# PSU.net
KiCad netlist of a schematic drawn in Altium Designer
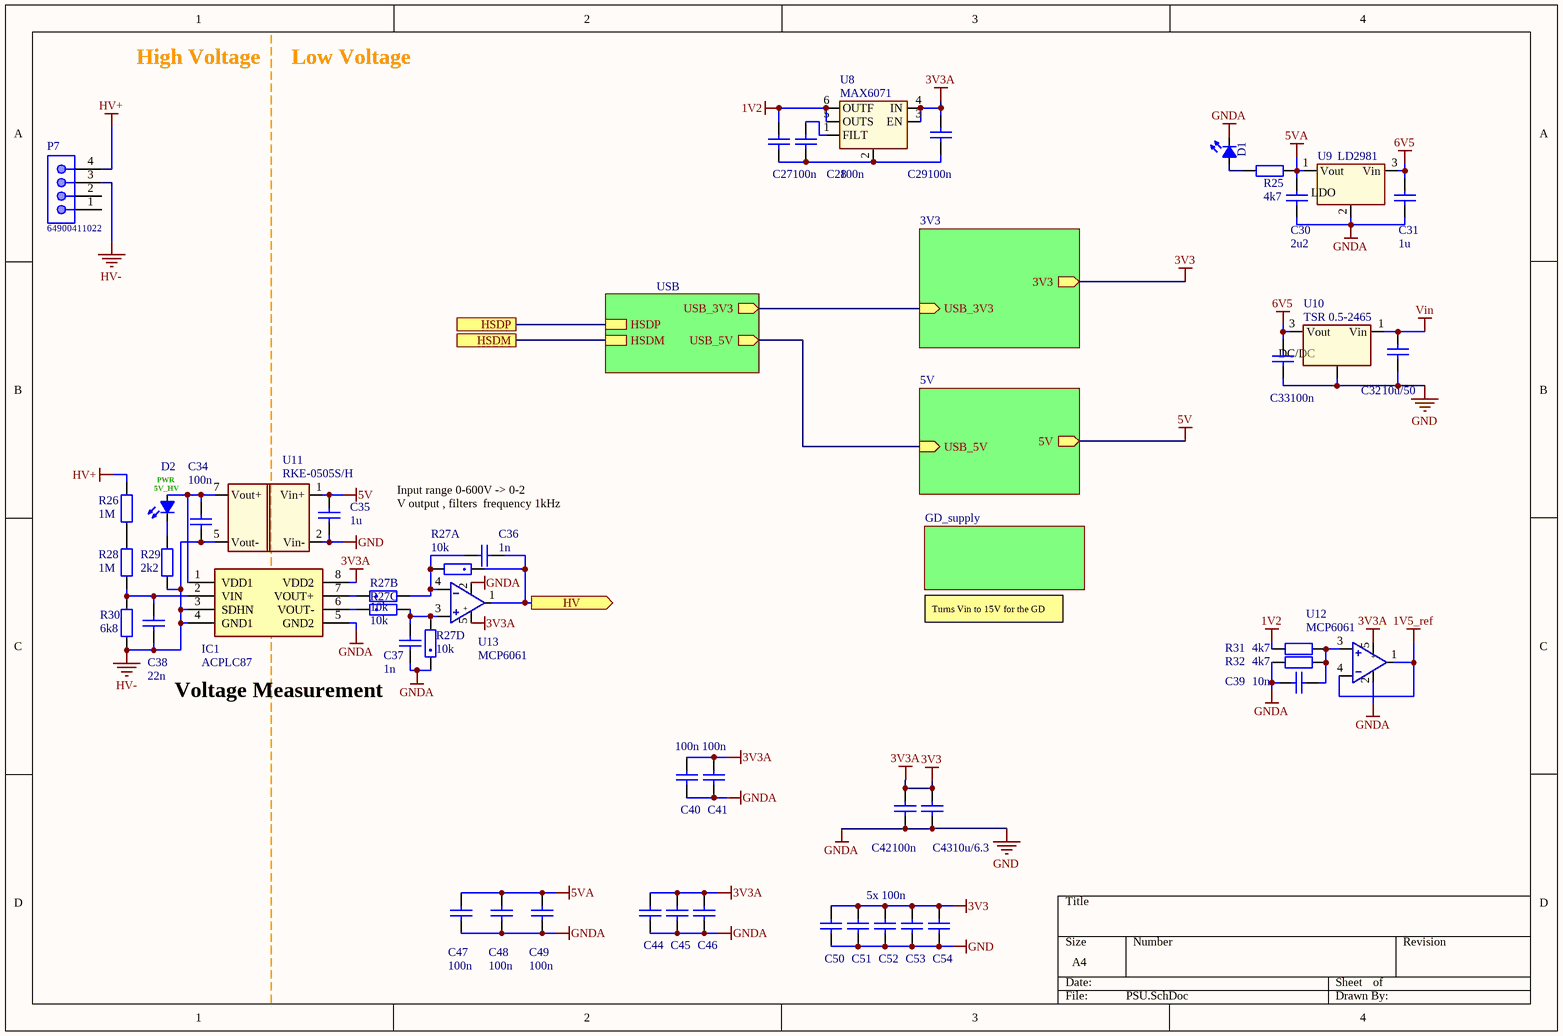
[diagram p0: PSU.SchDoc]

(export (version "E")
  (design (tool "Eeschema 10.0.6"))
  (components
    (comp (ref "C27")
      (value "100n")
      (footprint "C_0603")
      (description "cond")
      (libsource (lib "M_Standard") (part "C_MLCC"))
    )
    (comp (ref "C28")
      (value "100n")
      (footprint "C_0603")
      (description "cond")
      (libsource (lib "M_Standard") (part "C_MLCC"))
    )
    (comp (ref "C29")
      (value "100n")
      (footprint "C_0603")
      (description "cond")
      (libsource (lib "M_Standard") (part "C_MLCC"))
    )
    (comp (ref "C30")
      (value "2u2")
      (footprint "C_0805")
      (description "cond")
      (libsource (lib "M_Standard") (part "C_MLCC"))
    )
    (comp (ref "C31")
      (value "1u")
      (footprint "C_0805")
      (description "cond")
      (libsource (lib "M_Standard") (part "C_MLCC"))
    )
    (comp (ref "C32")
      (value "10u/50")
      (footprint "C_1210")
      (description "cond")
      (libsource (lib "M_Standard") (part "C_MLCC"))
    )
    (comp (ref "C33")
      (value "100n")
      (footprint "C_0603")
      (description "cond")
      (libsource (lib "M_Standard") (part "C_MLCC"))
    )
    (comp (ref "C34")
      (value "100n")
      (footprint "C_0603")
      (description "cond")
      (libsource (lib "M_Standard") (part "C_MLCC"))
    )
    (comp (ref "C35")
      (value "1u")
      (footprint "C_0805")
      (description "cond")
      (libsource (lib "M_Standard") (part "C_MLCC"))
    )
    (comp (ref "C36")
      (value "1n")
      (footprint "C_0603")
      (description "cond")
      (libsource (lib "M_Standard") (part "C_MLCC"))
    )
    (comp (ref "C37")
      (value "1n")
      (footprint "C_0603")
      (description "cond")
      (libsource (lib "M_Standard") (part "C_MLCC"))
    )
    (comp (ref "C38")
      (value "22n")
      (footprint "C_0603")
      (description "cond")
      (libsource (lib "M_Standard") (part "C_MLCC"))
    )
    (comp (ref "C39")
      (value "10n")
      (footprint "C_0603")
      (description "cond")
      (libsource (lib "M_Standard") (part "C_MLCC"))
    )
    (comp (ref "C40")
      (value "100n")
      (footprint "C_0603")
      (description "cond")
      (libsource (lib "M_Standard") (part "C_MLCC"))
    )
    (comp (ref "C41")
      (value "100n")
      (footprint "C_0603")
      (description "cond")
      (libsource (lib "M_Standard") (part "C_MLCC"))
    )
    (comp (ref "C42")
      (value "100n")
      (footprint "C_0603")
      (description "cond")
      (libsource (lib "M_Standard") (part "C_MLCC"))
    )
    (comp (ref "C43")
      (value "10u/6.3")
      (footprint "C_1210")
      (description "cond")
      (libsource (lib "M_Standard") (part "C_MLCC"))
    )
    (comp (ref "C44")
      (value "100n")
      (footprint "C_0603")
      (description "cond")
      (libsource (lib "M_Standard") (part "C_MLCC"))
    )
    (comp (ref "C45")
      (value "100n")
      (footprint "C_0603")
      (description "cond")
      (libsource (lib "M_Standard") (part "C_MLCC"))
    )
    (comp (ref "C46")
      (value "100n")
      (footprint "C_0603")
      (description "cond")
      (libsource (lib "M_Standard") (part "C_MLCC"))
    )
    (comp (ref "C47")
      (value "100n")
      (footprint "C_0603")
      (description "cond")
      (libsource (lib "M_Standard") (part "C_MLCC"))
    )
    (comp (ref "C48")
      (value "100n")
      (footprint "C_0603")
      (description "cond")
      (libsource (lib "M_Standard") (part "C_MLCC"))
    )
    (comp (ref "C49")
      (value "100n")
      (footprint "C_0603")
      (description "cond")
      (libsource (lib "M_Standard") (part "C_MLCC"))
    )
    (comp (ref "C50")
      (value "100n")
      (footprint "C_0603")
      (description "cond")
      (libsource (lib "M_Standard") (part "C_MLCC"))
    )
    (comp (ref "C51")
      (value "100n")
      (footprint "C_0603")
      (description "cond")
      (libsource (lib "M_Standard") (part "C_MLCC"))
    )
    (comp (ref "C52")
      (value "100n")
      (footprint "C_0603")
      (description "cond")
      (libsource (lib "M_Standard") (part "C_MLCC"))
    )
    (comp (ref "C53")
      (value "100n")
      (footprint "C_0603")
      (description "cond")
      (libsource (lib "M_Standard") (part "C_MLCC"))
    )
    (comp (ref "C54")
      (value "100n")
      (footprint "C_0603")
      (description "cond")
      (libsource (lib "M_Standard") (part "C_MLCC"))
    )
    (comp (ref "D1")
      (value "Green")
      (footprint "D0603")
      (description "LED diode")
      (libsource (lib "M_Standard") (part "D_LED small"))
    )
    (comp (ref "D2")
      (value "Green")
      (footprint "D0603")
      (description "LED diode")
      (libsource (lib "M_Standard") (part "D_LED small"))
    )
    (comp (ref "IC1")
      (value "ACPLC87")
      (footprint "IC_ACPL87")
      (description "isolation amplifier, 2V -1-GΩ  input")
      (fields
        (field (name "MANUFACTURER_PART_NUMBER") "ACPL-C87B-000E")
        (field (name "MOUSER PART NUMBER") "630-ACPL-C87B-000E")
      )
      (libsource (lib "M_Standard") (part "IC_ANA_AmpISO_ACPLC87"))
    )
    (comp (ref "P7")
      (value "64900411022")
      (footprint "64900411022")
      (fields (field (name "PUBLISHER") "Wurth Elektronik"))
      (libsource (lib "64900411022_Altium_WR-MPC4_rev19a") (part "64900411022"))
    )
    (comp (ref "R25")
      (value "4k7")
      (footprint "R_0603")
      (description "Resistor")
      (libsource (lib "M_Standard") (part "R_Uni"))
    )
    (comp (ref "R26")
      (value "1M")
      (footprint "R_1206")
      (description "Resistor")
      (libsource (lib "") (part "R_Uni_1"))
    )
    (comp (ref "R27")
      (value "10k")
      (footprint "R_Array  4D03")
      (description "Resistor array 4xR,  size 1206, 64mW")
      (libsource (lib "") (part "R_Array 4xR_1"))
    )
    (comp (ref "R28")
      (value "1M")
      (footprint "R_1206")
      (description "Resistor")
      (libsource (lib "") (part "R_Uni_1"))
    )
    (comp (ref "R29")
      (value "2k2")
      (footprint "R_0603")
      (description "Resistor")
      (libsource (lib "") (part "R_Uni_2"))
    )
    (comp (ref "R30")
      (value "6k8")
      (footprint "R_0603")
      (description "Resistor")
      (libsource (lib "") (part "R_Uni_1"))
    )
    (comp (ref "R31")
      (value "4k7")
      (footprint "R_0603")
      (description "Resistor")
      (libsource (lib "M_Standard") (part "R_Uni"))
    )
    (comp (ref "R32")
      (value "4k7")
      (footprint "R_0603")
      (description "Resistor")
      (libsource (lib "") (part "R_Uni_3"))
    )
    (comp (ref "U8")
      (value "MAX6071")
      (footprint "sot23-6")
      (description "3,00V ref")
      (libsource (lib "M_Standard") (part "IC_LDO_REF_MAX6071"))
    )
    (comp (ref "U9")
      (value "LD2981")
      (footprint "SOT89")
      (description "5V sot 89")
      (libsource (lib "M_Standard") (part "IC_LDO_LD2981"))
    )
    (comp (ref "U10")
      (value "TSR 0.5-2465")
      (footprint "M_Standard:DCDC_Wurth_173950x36")
      (description "DC/DC Out: 5V 1A  In: 9-36V")
      (libsource (lib "Voltage regulators") (part "PWR_TSR1-2450"))
    )
    (comp (ref "U11")
      (value "RKE-0505S/H")
      (footprint "DCDC_RKExxxxSH")
      (description "Dc/Dc ISO 3kV Recom RKE Series 200mA")
      (libsource (lib "M_Standard") (part "PWR_RKE_H"))
    )
    (comp (ref "U12")
      (value "MCP6061")
      (footprint "SOT23-5")
      (description "Vcc:1.8 -6V, Vo:150uA. Iq:60uA")
      (fields
        (field (name "MANUFACTURER") "Microchip")
        (field (name "MANUFACTURER PART NUMBER") "MCP6061T-E/OT")
      )
      (libsource (lib "M_Standard") (part "IC_ANA_MCP6061"))
    )
    (comp (ref "U13")
      (value "MCP6061")
      (footprint "SOT23-5")
      (description "Vcc:1.8 -6V, Vo:150uA. Iq:60uA")
      (fields
        (field (name "MANUFACTURER") "Microchip")
        (field (name "MANUFACTURER PART NUMBER") "MCP6061T-E/OT")
      )
      (libsource (lib "M_Standard") (part "IC_ANA_MCP6061"))
    )
  )
  (nets
    (net (code "3") (name "/HV") (class "Default")
      (node (ref "C36") (pin "2") (pinfunction "2_2") (pintype "passive"))
      (node (ref "R27") (pin "1") (pinfunction "1_1") (pintype "passive"))
      (node (ref "U13") (pin "1") (pinfunction "out_A_1") (pintype "passive"))
    )
    (net (code "6") (name "1V2") (class "Default")
      (node (ref "C27") (pin "2") (pinfunction "2_2") (pintype "passive"))
      (node (ref "R31") (pin "1") (pinfunction "1_1") (pintype "passive"))
      (node (ref "U8") (pin "5") (pinfunction "OUTS_5") (pintype "passive"))
      (node (ref "U8") (pin "6") (pinfunction "OUTF_6") (pintype "passive"))
    )
    (net (code "7") (name "1V5_ref") (class "Default")
      (node (ref "U12") (pin "1") (pinfunction "out_A_1") (pintype "passive"))
      (node (ref "U12") (pin "4") (pinfunction "IN-_4") (pintype "passive"))
    )
    (net (code "8") (name "3V3") (class "Default")
      (node (ref "C29") (pin "2") (pinfunction "2_2") (pintype "passive"))
      (node (ref "C40") (pin "2") (pinfunction "2_2") (pintype "passive"))
      (node (ref "C41") (pin "2") (pinfunction "2_2") (pintype "passive"))
      (node (ref "C42") (pin "2") (pinfunction "2_2") (pintype "passive"))
      (node (ref "C43") (pin "1") (pinfunction "1_1") (pintype "passive"))
      (node (ref "C44") (pin "2") (pinfunction "2_2") (pintype "passive"))
      (node (ref "C45") (pin "2") (pinfunction "2_2") (pintype "passive"))
      (node (ref "C46") (pin "2") (pinfunction "2_2") (pintype "passive"))
      (node (ref "C50") (pin "2") (pinfunction "2_2") (pintype "passive"))
      (node (ref "C51") (pin "2") (pinfunction "2_2") (pintype "passive"))
      (node (ref "C52") (pin "2") (pinfunction "2_2") (pintype "passive"))
      (node (ref "C53") (pin "2") (pinfunction "2_2") (pintype "passive"))
      (node (ref "C54") (pin "2") (pinfunction "2_2") (pintype "passive"))
      (node (ref "IC1") (pin "8") (pinfunction "VDD2_8") (pintype "passive"))
      (node (ref "U12") (pin "5") (pinfunction "vdd_5") (pintype "passive"))
      (node (ref "U13") (pin "5") (pinfunction "vdd_5") (pintype "passive"))
      (node (ref "U8") (pin "3") (pinfunction "EN_3") (pintype "passive"))
      (node (ref "U8") (pin "4") (pinfunction "IN_4") (pintype "passive"))
    )
    (net (code "9") (name "5V") (class "Default")
      (node (ref "C35") (pin "1") (pinfunction "1_1") (pintype "passive"))
      (node (ref "U11") (pin "1") (pinfunction "Vin+_1") (pintype "passive"))
    )
    (net (code "10") (name "5VA") (class "Default")
      (node (ref "C30") (pin "1") (pinfunction "1_1") (pintype "passive"))
      (node (ref "C47") (pin "1") (pinfunction "1_1") (pintype "passive"))
      (node (ref "C48") (pin "1") (pinfunction "1_1") (pintype "passive"))
      (node (ref "C49") (pin "1") (pinfunction "1_1") (pintype "passive"))
      (node (ref "R25") (pin "2") (pinfunction "2_2") (pintype "passive"))
      (node (ref "U9") (pin "1") (pinfunction "Vout_1") (pintype "passive"))
    )
    (net (code "11") (name "6V5") (class "Default")
      (node (ref "C31") (pin "2") (pinfunction "2_2") (pintype "passive"))
      (node (ref "C33") (pin "2") (pinfunction "2_2") (pintype "passive"))
      (node (ref "U10") (pin "3") (pinfunction "Vout_3") (pintype "passive"))
      (node (ref "U9") (pin "3") (pinfunction "Vin_3") (pintype "passive"))
    )
    (net (code "12") (name "GND") (class "Default")
      (node (ref "C30") (pin "2") (pinfunction "2_2") (pintype "passive"))
      (node (ref "C31") (pin "1") (pinfunction "1_1") (pintype "passive"))
      (node (ref "C32") (pin "2") (pinfunction "2_2") (pintype "passive"))
      (node (ref "C33") (pin "1") (pinfunction "1_1") (pintype "passive"))
      (node (ref "C35") (pin "2") (pinfunction "2_2") (pintype "passive"))
      (node (ref "C37") (pin "2") (pinfunction "2_2") (pintype "passive"))
      (node (ref "C39") (pin "2") (pinfunction "2_2") (pintype "passive"))
      (node (ref "C40") (pin "1") (pinfunction "1_1") (pintype "passive"))
      (node (ref "C41") (pin "1") (pinfunction "1_1") (pintype "passive"))
      (node (ref "C42") (pin "1") (pinfunction "1_1") (pintype "passive"))
      (node (ref "C43") (pin "2") (pinfunction "2_2") (pintype "passive"))
      (node (ref "C44") (pin "1") (pinfunction "1_1") (pintype "passive"))
      (node (ref "C45") (pin "1") (pinfunction "1_1") (pintype "passive"))
      (node (ref "C46") (pin "1") (pinfunction "1_1") (pintype "passive"))
      (node (ref "C47") (pin "2") (pinfunction "2_2") (pintype "passive"))
      (node (ref "C48") (pin "2") (pinfunction "2_2") (pintype "passive"))
      (node (ref "C49") (pin "2") (pinfunction "2_2") (pintype "passive"))
      (node (ref "C50") (pin "1") (pinfunction "1_1") (pintype "passive"))
      (node (ref "C51") (pin "1") (pinfunction "1_1") (pintype "passive"))
      (node (ref "C52") (pin "1") (pinfunction "1_1") (pintype "passive"))
      (node (ref "C53") (pin "1") (pinfunction "1_1") (pintype "passive"))
      (node (ref "C54") (pin "1") (pinfunction "1_1") (pintype "passive"))
      (node (ref "D1") (pin "1") (pinfunction "K_1") (pintype "passive"))
      (node (ref "IC1") (pin "5") (pinfunction "GND2_5") (pintype "passive"))
      (node (ref "R27") (pin "4") (pinfunction "4_4") (pintype "passive"))
      (node (ref "R32") (pin "2") (pinfunction "2_2") (pintype "passive"))
      (node (ref "U10") (pin "2") (pinfunction "GND_2") (pintype "passive"))
      (node (ref "U11") (pin "2") (pinfunction "Vin-_2") (pintype "passive"))
      (node (ref "U12") (pin "2") (pinfunction "vss_2") (pintype "passive"))
      (node (ref "U13") (pin "2") (pinfunction "vss_2") (pintype "passive"))
      (node (ref "U9") (pin "2") (pinfunction "GND_2") (pintype "passive"))
    )
    (net (code "13") (name "HV+") (class "Default")
      (node (ref "P7") (pin "4") (pinfunction "4_4") (pintype "passive"))
      (node (ref "R26") (pin "1") (pinfunction "1_1") (pintype "passive"))
    )
    (net (code "14") (name "HV-") (class "Default")
      (node (ref "C34") (pin "2") (pinfunction "2_2") (pintype "passive"))
      (node (ref "C38") (pin "2") (pinfunction "2_2") (pintype "passive"))
      (node (ref "IC1") (pin "3") (pinfunction "SDHN_3") (pintype "passive"))
      (node (ref "IC1") (pin "4") (pinfunction "GND1_4") (pintype "passive"))
      (node (ref "P7") (pin "3") (pinfunction "3_3") (pintype "passive"))
      (node (ref "R29") (pin "1") (pinfunction "1_1") (pintype "passive"))
      (node (ref "R30") (pin "2") (pinfunction "2_2") (pintype "passive"))
      (node (ref "U11") (pin "5") (pinfunction "Vout-_5") (pintype "passive"))
    )
    (net (code "15") (name "Net-(D1-A)") (class "Default")
      (node (ref "D1") (pin "2") (pinfunction "A_2") (pintype "passive"))
      (node (ref "R25") (pin "1") (pinfunction "1_1") (pintype "passive"))
    )
    (net (code "16") (name "Net-(D2-A)") (class "Default")
      (node (ref "C34") (pin "1") (pinfunction "1_1") (pintype "passive"))
      (node (ref "D2") (pin "2") (pinfunction "A_2") (pintype "passive"))
      (node (ref "IC1") (pin "1") (pinfunction "VDD1_1") (pintype "passive"))
      (node (ref "U11") (pin "7") (pinfunction "Vout+_7") (pintype "passive"))
    )
    (net (code "17") (name "Net-(D2-K)") (class "Default")
      (node (ref "D2") (pin "1") (pinfunction "K_1") (pintype "passive"))
      (node (ref "R29") (pin "2") (pinfunction "2_2") (pintype "passive"))
    )
    (net (code "18") (name "Net-(IC1-VIN)") (class "Default")
      (node (ref "C38") (pin "1") (pinfunction "1_1") (pintype "passive"))
      (node (ref "IC1") (pin "2") (pinfunction "VIN_2") (pintype "passive"))
      (node (ref "R28") (pin "2") (pinfunction "2_2") (pintype "passive"))
      (node (ref "R30") (pin "1") (pinfunction "1_1") (pintype "passive"))
    )
    (net (code "19") (name "Net-(IC1-VOUT+)") (class "Default")
      (node (ref "IC1") (pin "7") (pinfunction "VOUT+_7") (pintype "passive"))
      (node (ref "R27") (pin "2") (pinfunction "2_2") (pintype "passive"))
    )
    (net (code "20") (name "Net-(IC1-VOUT-)") (class "Default")
      (node (ref "IC1") (pin "6") (pinfunction "VOUT-_6") (pintype "passive"))
      (node (ref "R27") (pin "3") (pinfunction "3_3") (pintype "passive"))
    )
    (net (code "21") (name "Net-(R26-Pad2)") (class "Default")
      (node (ref "R26") (pin "2") (pinfunction "2_2") (pintype "passive"))
      (node (ref "R28") (pin "1") (pinfunction "1_1") (pintype "passive"))
    )
    (net (code "22") (name "Net-(U8-FILT)") (class "Default")
      (node (ref "C28") (pin "2") (pinfunction "2_2") (pintype "passive"))
      (node (ref "U8") (pin "1") (pinfunction "FILT_1") (pintype "passive"))
    )
    (net (code "23") (name "Net-(U8-GND)") (class "Default")
      (node (ref "C27") (pin "1") (pinfunction "1_1") (pintype "passive"))
      (node (ref "C28") (pin "1") (pinfunction "1_1") (pintype "passive"))
      (node (ref "C29") (pin "1") (pinfunction "1_1") (pintype "passive"))
      (node (ref "U8") (pin "2") (pinfunction "GND_2") (pintype "passive"))
    )
    (net (code "24") (name "Net-(U12-IN+)") (class "Default")
      (node (ref "C39") (pin "1") (pinfunction "1_1") (pintype "passive"))
      (node (ref "R31") (pin "2") (pinfunction "2_2") (pintype "passive"))
      (node (ref "R32") (pin "1") (pinfunction "1_1") (pintype "passive"))
      (node (ref "U12") (pin "3") (pinfunction "IN+_3") (pintype "passive"))
    )
    (net (code "25") (name "Net-(U13-IN+)") (class "Default")
      (node (ref "C37") (pin "1") (pinfunction "1_1") (pintype "passive"))
      (node (ref "R27") (pin "5") (pinfunction "5_5") (pintype "passive"))
      (node (ref "R27") (pin "6") (pinfunction "6_6") (pintype "passive"))
      (node (ref "U13") (pin "3") (pinfunction "IN+_3") (pintype "passive"))
    )
    (net (code "26") (name "Net-(U13-IN-)") (class "Default")
      (node (ref "C36") (pin "1") (pinfunction "1_1") (pintype "passive"))
      (node (ref "R27") (pin "7") (pinfunction "7_7") (pintype "passive"))
      (node (ref "R27") (pin "8") (pinfunction "8_8") (pintype "passive"))
      (node (ref "U13") (pin "4") (pinfunction "IN-_4") (pintype "passive"))
    )
    (net (code "27") (name "Vin") (class "Default")
      (node (ref "C32") (pin "1") (pinfunction "1_1") (pintype "passive"))
      (node (ref "U10") (pin "1") (pinfunction "Vin_1") (pintype "passive"))
    )
    (net (code "28") (name "unconnected-(P7-Pad1)") (class "Default")
      (node (ref "P7") (pin "1") (pinfunction "1_1") (pintype "passive"))
    )
    (net (code "29") (name "unconnected-(P7-Pad2)") (class "Default")
      (node (ref "P7") (pin "2") (pinfunction "2_2") (pintype "passive"))
    )
  )
)
